# eGAN-FET-module_Connectors.net
KiCad netlist of a schematic drawn in Altium Designer
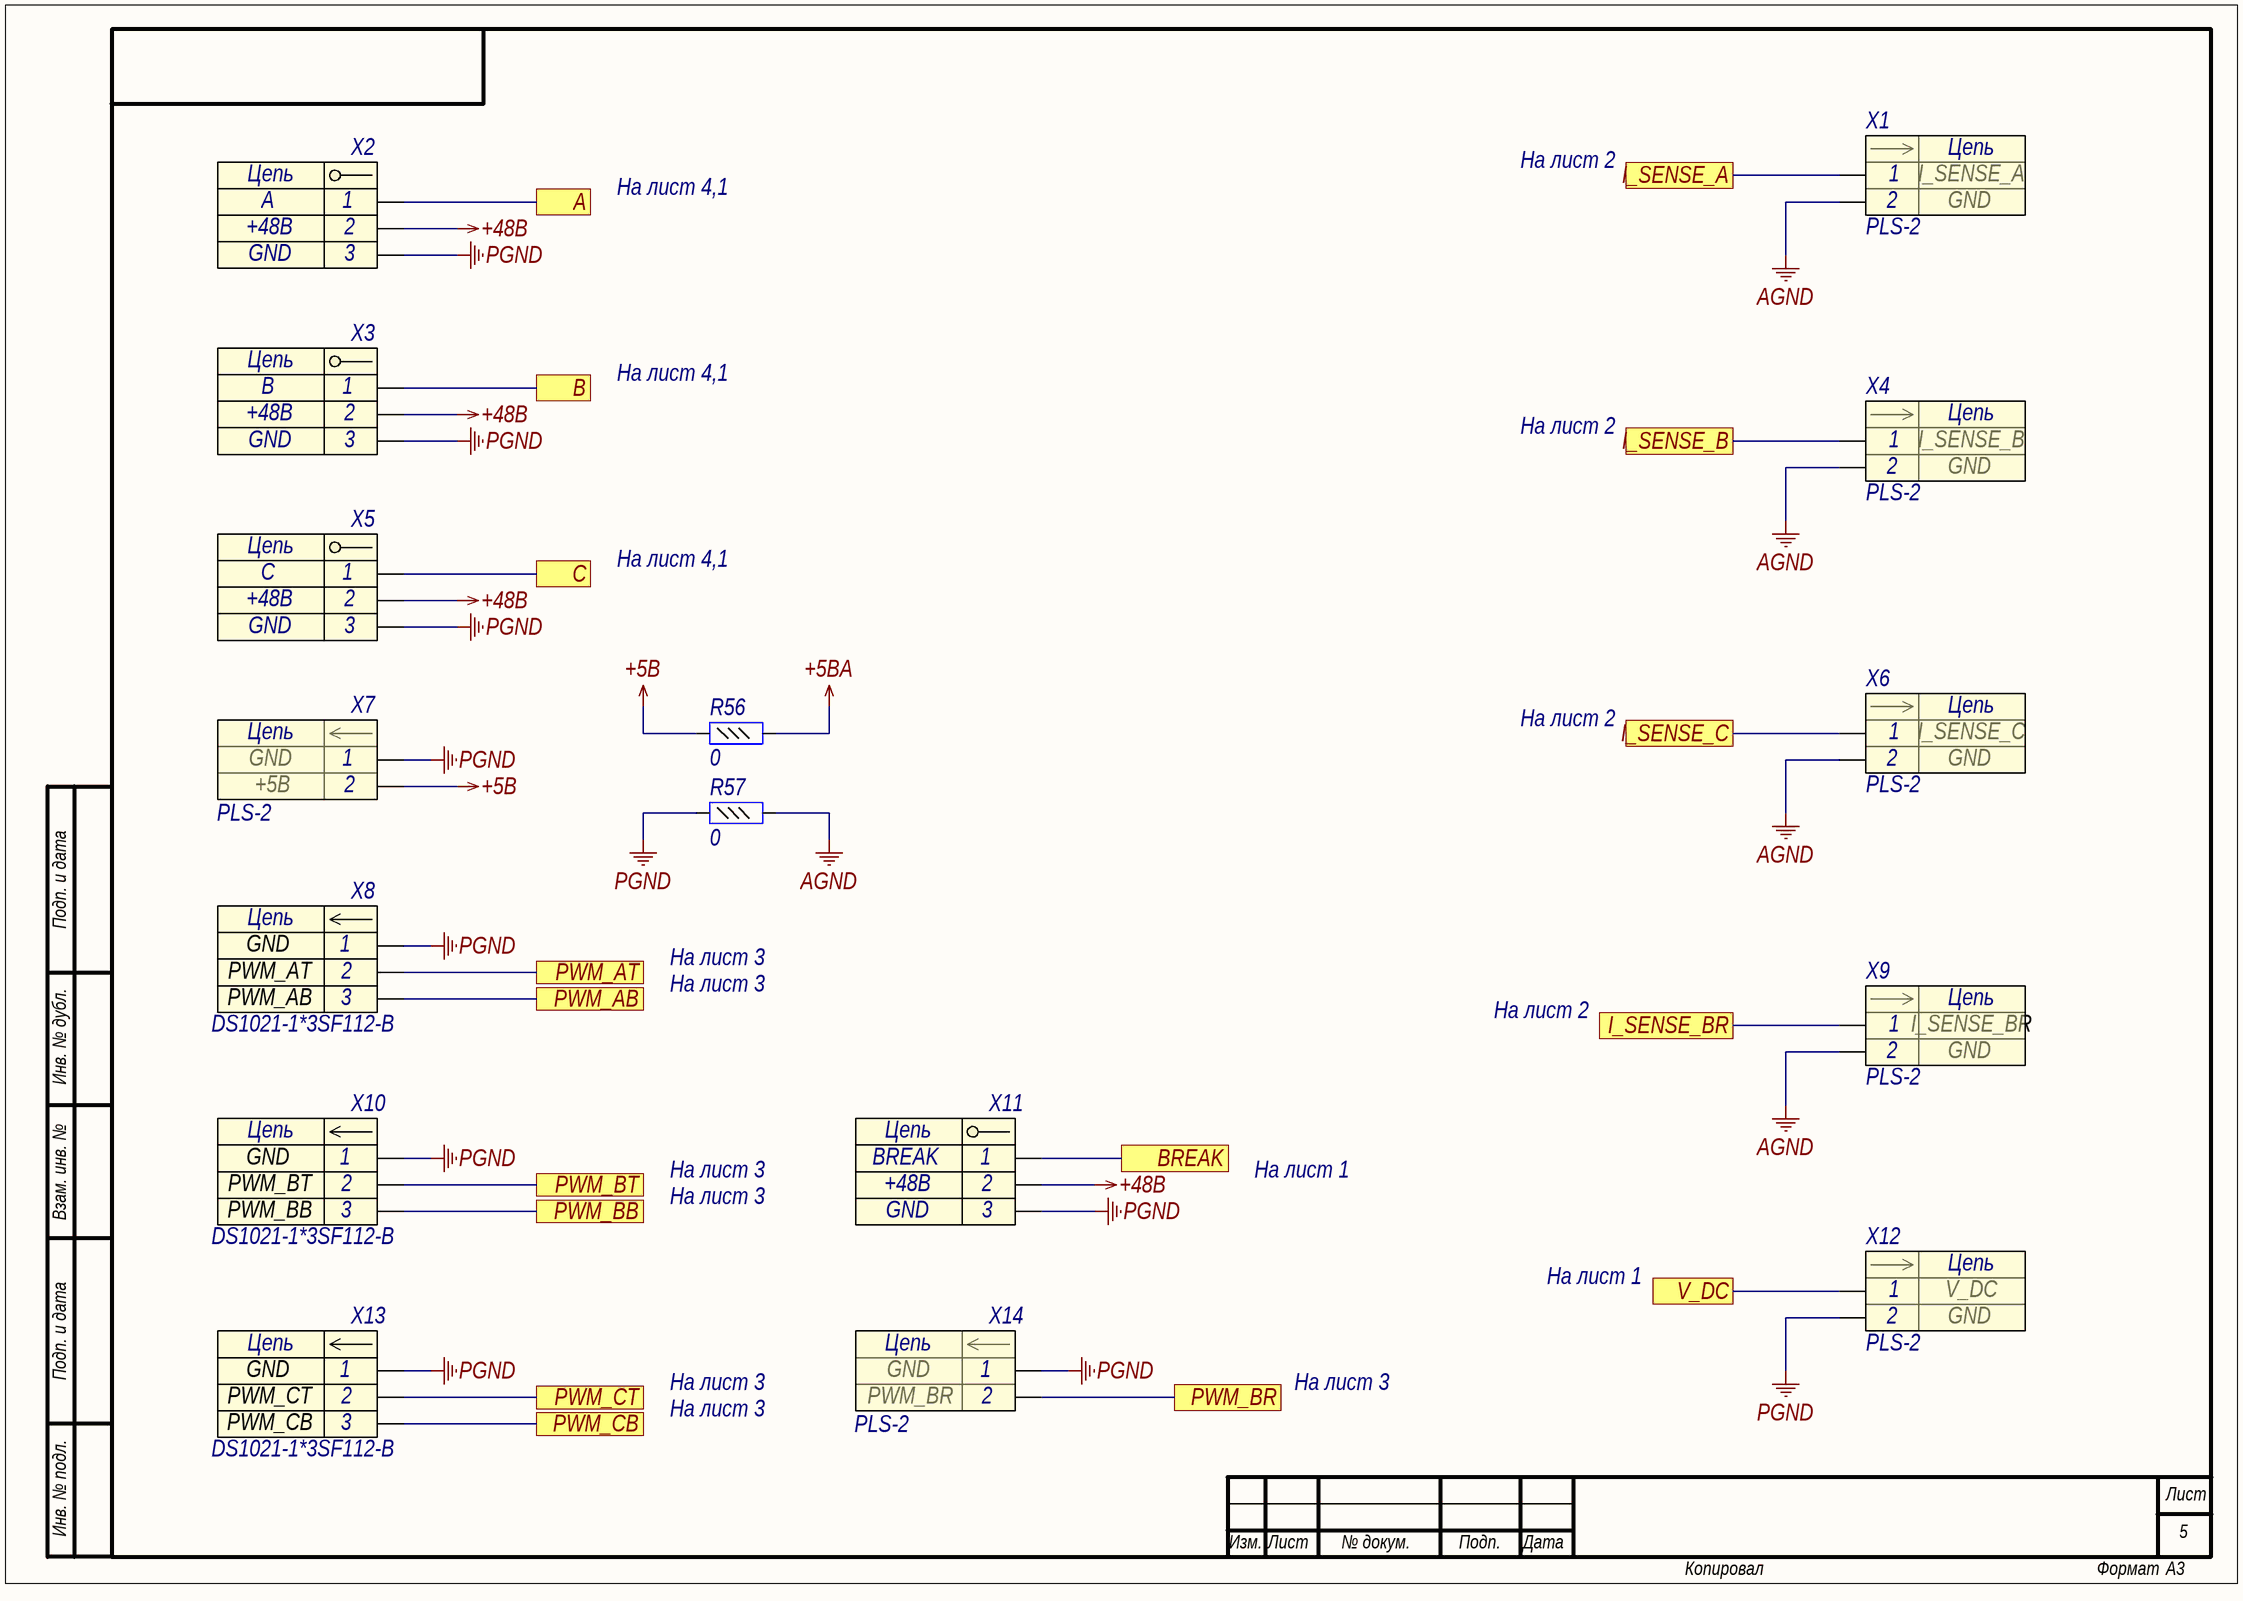
[diagram p0: eGAN-FET-module_Connectors.SchDoc]

(export (version "E")
  (design (tool "Eeschema 10.0.6"))
  (components
    (comp (ref "R56")
      (value "0")
      (footprint "R0402")
      (description "Резистор")
      (fields (field (name "PART NUMBER") "RC0402FR-070RL") (field (name "POWER") "0,062Вт"))
      (libsource (lib "MOP44") (part "Resistor_0,062Вт"))
    )
    (comp (ref "R57")
      (value "0")
      (footprint "R0402")
      (description "Резистор")
      (fields (field (name "PART NUMBER") "RC0402FR-070RL") (field (name "POWER") "0,062Вт"))
      (libsource (lib "MOP44") (part "Resistor_0,062Вт"))
    )
    (comp (ref "X1")
      (value "~")
      (footprint "PLS-2")
      (description "Разъем - 2 конт. вилка")
      (fields (field (name "PART NAME") "PLS-2"))
      (libsource (lib "MOP44") (part "Header_2_plg"))
    )
    (comp (ref "X2")
      (value "~")
      (footprint "KUBO_3")
      (description "Разъем - 3 конт. клеммник")
      (libsource (lib "MOP44") (part "Header_3_trm"))
    )
    (comp (ref "X3")
      (value "~")
      (footprint "KUBO_3")
      (description "Разъем - 3 конт. клеммник")
      (libsource (lib "MOP44") (part "Header_3_trm"))
    )
    (comp (ref "X4")
      (value "~")
      (footprint "PLS-2")
      (description "Разъем - 2 конт. вилка")
      (fields (field (name "PART NAME") "PLS-2"))
      (libsource (lib "MOP44") (part "Header_2_plg"))
    )
    (comp (ref "X5")
      (value "~")
      (footprint "KUBO_3")
      (description "Разъем - 3 конт. клеммник")
      (libsource (lib "MOP44") (part "Header_3_trm"))
    )
    (comp (ref "X6")
      (value "~")
      (footprint "PLS-2")
      (description "Разъем - 2 конт. вилка")
      (fields (field (name "PART NAME") "PLS-2"))
      (libsource (lib "MOP44") (part "Header_2_plg"))
    )
    (comp (ref "X7")
      (value "~")
      (footprint "PLS-2")
      (description "Разъем - 2 конт. вилка")
      (fields (field (name "PART NAME") "PLS-2"))
      (libsource (lib "") (part "Header_2_plg_1"))
    )
    (comp (ref "X8")
      (value "DS1021-1*3SF112-B")
      (footprint "PLS-3")
      (description "Разъем - 3 конт. вилка")
      (fields (field (name "PART NUMBER") "DS1021-1*3SF112-B"))
      (libsource (lib "MOP44") (part "Header_3_plg"))
    )
    (comp (ref "X9")
      (value "~")
      (footprint "PLS-2")
      (description "Разъем - 2 конт. вилка")
      (fields (field (name "PART NAME") "PLS-2"))
      (libsource (lib "MOP44") (part "Header_2_plg"))
    )
    (comp (ref "X10")
      (value "DS1021-1*3SF112-B")
      (footprint "PLS-3")
      (description "Разъем - 3 конт. вилка")
      (fields (field (name "PART NUMBER") "DS1021-1*3SF112-B"))
      (libsource (lib "MOP44") (part "Header_3_plg"))
    )
    (comp (ref "X11")
      (value "~")
      (footprint "KUBO_3")
      (description "Разъем - 3 конт. клеммник")
      (libsource (lib "MOP44") (part "Header_3_trm"))
    )
    (comp (ref "X12")
      (value "~")
      (footprint "PLS-2")
      (description "Разъем - 2 конт. вилка")
      (fields (field (name "PART NAME") "PLS-2"))
      (libsource (lib "MOP44") (part "Header_2_plg"))
    )
    (comp (ref "X13")
      (value "DS1021-1*3SF112-B")
      (footprint "PLS-3")
      (description "Разъем - 3 конт. вилка")
      (fields (field (name "PART NUMBER") "DS1021-1*3SF112-B"))
      (libsource (lib "MOP44") (part "Header_3_plg"))
    )
    (comp (ref "X14")
      (value "~")
      (footprint "PLS-2")
      (description "Разъем - 2 конт. вилка")
      (fields (field (name "PART NAME") "PLS-2"))
      (libsource (lib "") (part "Header_2_plg_1"))
    )
  )
  (nets
    (net (code "1") (name "+5B") (class "Default")
      (node (ref "R56") (pin "1") (pinfunction "1_1") (pintype "passive"))
      (node (ref "X7") (pin "2") (pinfunction "2_2") (pintype "passive"))
    )
    (net (code "2") (name "+5BA") (class "Default")
      (node (ref "R56") (pin "2") (pinfunction "2_2") (pintype "passive"))
    )
    (net (code "3") (name "+48B") (class "Default")
      (node (ref "X11") (pin "2") (pinfunction "2_2") (pintype "passive"))
      (node (ref "X2") (pin "2") (pinfunction "2_2") (pintype "passive"))
      (node (ref "X3") (pin "2") (pinfunction "2_2") (pintype "passive"))
      (node (ref "X5") (pin "2") (pinfunction "2_2") (pintype "passive"))
    )
    (net (code "4") (name "/A") (class "Default")
      (node (ref "X2") (pin "1") (pinfunction "1_1") (pintype "passive"))
    )
    (net (code "5") (name "/B") (class "Default")
      (node (ref "X3") (pin "1") (pinfunction "1_1") (pintype "passive"))
    )
    (net (code "6") (name "/BREAK") (class "Default")
      (node (ref "X11") (pin "1") (pinfunction "1_1") (pintype "passive"))
    )
    (net (code "7") (name "/C") (class "Default")
      (node (ref "X5") (pin "1") (pinfunction "1_1") (pintype "passive"))
    )
    (net (code "8") (name "/I_SENSE_A") (class "Default")
      (node (ref "X1") (pin "1") (pinfunction "1_1") (pintype "passive"))
    )
    (net (code "9") (name "/I_SENSE_B") (class "Default")
      (node (ref "X4") (pin "1") (pinfunction "1_1") (pintype "passive"))
    )
    (net (code "10") (name "/I_SENSE_BR") (class "Default")
      (node (ref "X9") (pin "1") (pinfunction "1_1") (pintype "passive"))
    )
    (net (code "11") (name "/I_SENSE_C") (class "Default")
      (node (ref "X6") (pin "1") (pinfunction "1_1") (pintype "passive"))
    )
    (net (code "12") (name "/PWM_AB") (class "Default")
      (node (ref "X8") (pin "3") (pinfunction "3_3") (pintype "passive"))
    )
    (net (code "13") (name "/PWM_AT") (class "Default")
      (node (ref "X8") (pin "2") (pinfunction "2_2") (pintype "passive"))
    )
    (net (code "14") (name "/PWM_BB") (class "Default")
      (node (ref "X10") (pin "3") (pinfunction "3_3") (pintype "passive"))
    )
    (net (code "15") (name "/PWM_BR") (class "Default")
      (node (ref "X14") (pin "2") (pinfunction "2_2") (pintype "passive"))
    )
    (net (code "16") (name "/PWM_BT") (class "Default")
      (node (ref "X10") (pin "2") (pinfunction "2_2") (pintype "passive"))
    )
    (net (code "17") (name "/PWM_CB") (class "Default")
      (node (ref "X13") (pin "3") (pinfunction "3_3") (pintype "passive"))
    )
    (net (code "18") (name "/PWM_CT") (class "Default")
      (node (ref "X13") (pin "2") (pinfunction "2_2") (pintype "passive"))
    )
    (net (code "19") (name "/V_DC") (class "Default")
      (node (ref "X12") (pin "1") (pinfunction "1_1") (pintype "passive"))
    )
    (net (code "20") (name "AGND") (class "Default")
      (node (ref "R57") (pin "2") (pinfunction "2_2") (pintype "passive"))
      (node (ref "X1") (pin "2") (pinfunction "2_2") (pintype "passive"))
      (node (ref "X4") (pin "2") (pinfunction "2_2") (pintype "passive"))
      (node (ref "X6") (pin "2") (pinfunction "2_2") (pintype "passive"))
      (node (ref "X9") (pin "2") (pinfunction "2_2") (pintype "passive"))
    )
    (net (code "21") (name "PGND") (class "Default")
      (node (ref "R57") (pin "1") (pinfunction "1_1") (pintype "passive"))
      (node (ref "X10") (pin "1") (pinfunction "1_1") (pintype "passive"))
      (node (ref "X11") (pin "3") (pinfunction "3_3") (pintype "passive"))
      (node (ref "X12") (pin "2") (pinfunction "2_2") (pintype "passive"))
      (node (ref "X13") (pin "1") (pinfunction "1_1") (pintype "passive"))
      (node (ref "X14") (pin "1") (pinfunction "1_1") (pintype "passive"))
      (node (ref "X2") (pin "3") (pinfunction "3_3") (pintype "passive"))
      (node (ref "X3") (pin "3") (pinfunction "3_3") (pintype "passive"))
      (node (ref "X5") (pin "3") (pinfunction "3_3") (pintype "passive"))
      (node (ref "X7") (pin "1") (pinfunction "1_1") (pintype "passive"))
      (node (ref "X8") (pin "1") (pinfunction "1_1") (pintype "passive"))
    )
  )
)
